# 5_Controller_A20_SSRs.net
KiCad netlist of a schematic drawn in Altium Designer
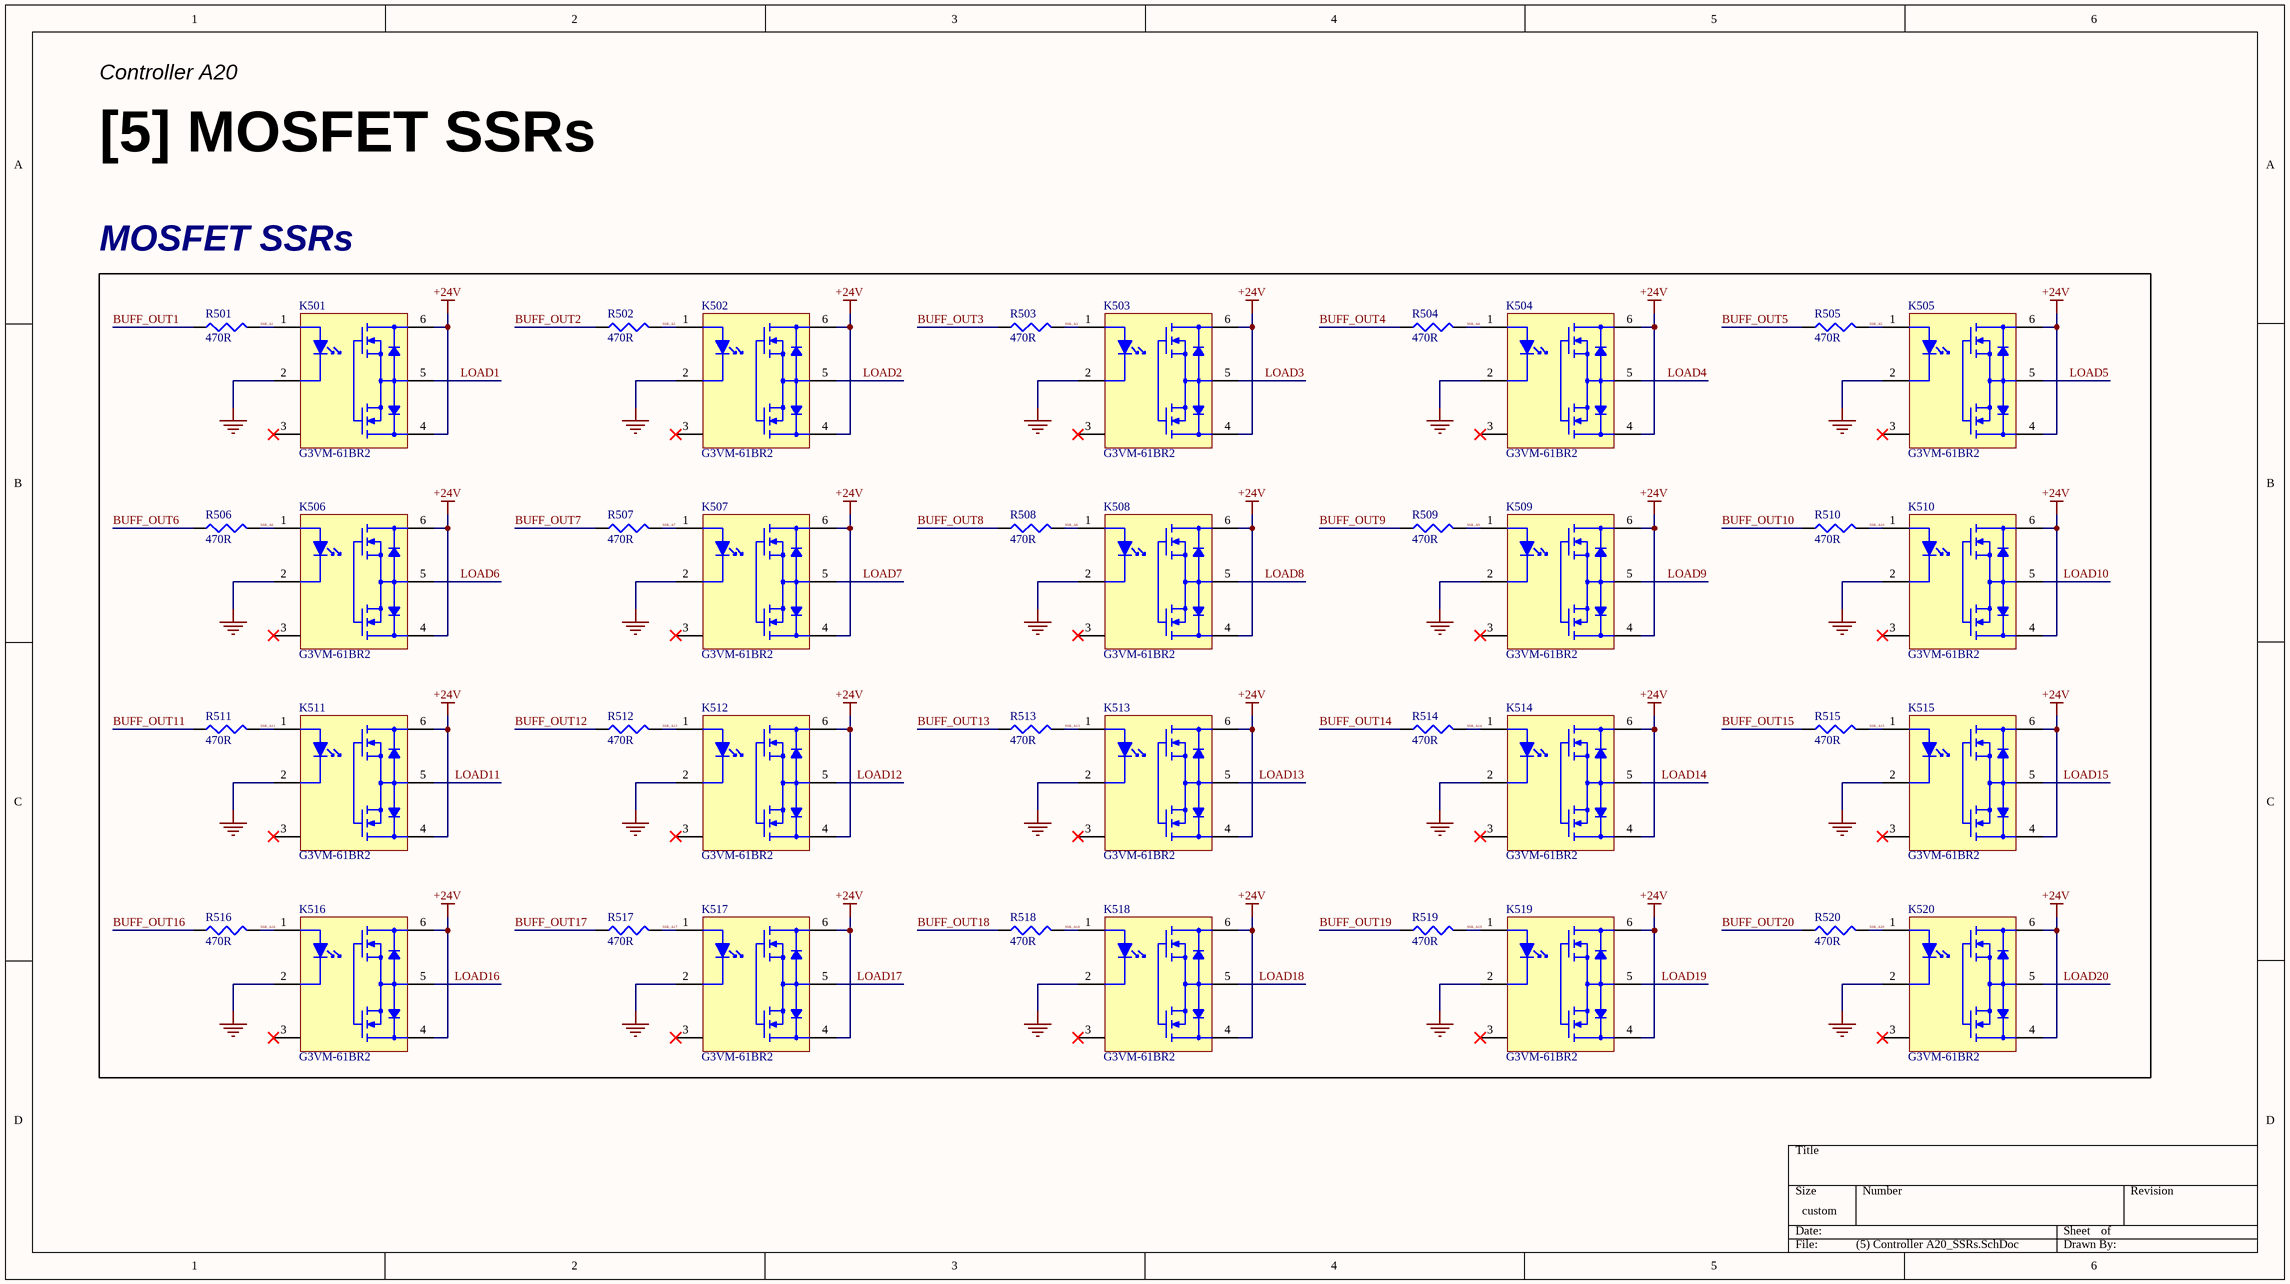
[diagram p0: (5) Controller A20_SSRs.SchDoc]

(export (version "E")
  (design (tool "Eeschema 10.0.6"))
  (components
    (comp (ref "K501")
      (value "G3VM-61BR2")
      (footprint "DIP6")
      (description "2.5kV 60V 1.64V DIP-6 Solid State Relays (SSR) RoHS")
      (fields (field (name "MANUFACTURER") "Omron Electronics Inc-EMC Div"))
      (libsource (lib "Symbols") (part "G3VM-61BR2 60V 4/8 A SSR"))
    )
    (comp (ref "K502")
      (value "G3VM-61BR2")
      (footprint "DIP6")
      (description "2.5kV 60V 1.64V DIP-6 Solid State Relays (SSR) RoHS")
      (fields (field (name "MANUFACTURER") "Omron Electronics Inc-EMC Div"))
      (libsource (lib "Symbols") (part "G3VM-61BR2 60V 4/8 A SSR"))
    )
    (comp (ref "K503")
      (value "G3VM-61BR2")
      (footprint "DIP6")
      (description "2.5kV 60V 1.64V DIP-6 Solid State Relays (SSR) RoHS")
      (fields (field (name "MANUFACTURER") "Omron Electronics Inc-EMC Div"))
      (libsource (lib "Symbols") (part "G3VM-61BR2 60V 4/8 A SSR"))
    )
    (comp (ref "K504")
      (value "G3VM-61BR2")
      (footprint "DIP6")
      (description "2.5kV 60V 1.64V DIP-6 Solid State Relays (SSR) RoHS")
      (fields (field (name "MANUFACTURER") "Omron Electronics Inc-EMC Div"))
      (libsource (lib "Symbols") (part "G3VM-61BR2 60V 4/8 A SSR"))
    )
    (comp (ref "K505")
      (value "G3VM-61BR2")
      (footprint "DIP6")
      (description "2.5kV 60V 1.64V DIP-6 Solid State Relays (SSR) RoHS")
      (fields (field (name "MANUFACTURER") "Omron Electronics Inc-EMC Div"))
      (libsource (lib "Symbols") (part "G3VM-61BR2 60V 4/8 A SSR"))
    )
    (comp (ref "K506")
      (value "G3VM-61BR2")
      (footprint "DIP6")
      (description "2.5kV 60V 1.64V DIP-6 Solid State Relays (SSR) RoHS")
      (fields (field (name "MANUFACTURER") "Omron Electronics Inc-EMC Div"))
      (libsource (lib "Symbols") (part "G3VM-61BR2 60V 4/8 A SSR"))
    )
    (comp (ref "K507")
      (value "G3VM-61BR2")
      (footprint "DIP6")
      (description "2.5kV 60V 1.64V DIP-6 Solid State Relays (SSR) RoHS")
      (fields (field (name "MANUFACTURER") "Omron Electronics Inc-EMC Div"))
      (libsource (lib "Symbols") (part "G3VM-61BR2 60V 4/8 A SSR"))
    )
    (comp (ref "K508")
      (value "G3VM-61BR2")
      (footprint "DIP6")
      (description "2.5kV 60V 1.64V DIP-6 Solid State Relays (SSR) RoHS")
      (fields (field (name "MANUFACTURER") "Omron Electronics Inc-EMC Div"))
      (libsource (lib "Symbols") (part "G3VM-61BR2 60V 4/8 A SSR"))
    )
    (comp (ref "K509")
      (value "G3VM-61BR2")
      (footprint "DIP6")
      (description "2.5kV 60V 1.64V DIP-6 Solid State Relays (SSR) RoHS")
      (fields (field (name "MANUFACTURER") "Omron Electronics Inc-EMC Div"))
      (libsource (lib "Symbols") (part "G3VM-61BR2 60V 4/8 A SSR"))
    )
    (comp (ref "K510")
      (value "G3VM-61BR2")
      (footprint "DIP6")
      (description "2.5kV 60V 1.64V DIP-6 Solid State Relays (SSR) RoHS")
      (fields (field (name "MANUFACTURER") "Omron Electronics Inc-EMC Div"))
      (libsource (lib "Symbols") (part "G3VM-61BR2 60V 4/8 A SSR"))
    )
    (comp (ref "K511")
      (value "G3VM-61BR2")
      (footprint "DIP6")
      (description "2.5kV 60V 1.64V DIP-6 Solid State Relays (SSR) RoHS")
      (fields (field (name "MANUFACTURER") "Omron Electronics Inc-EMC Div"))
      (libsource (lib "Symbols") (part "G3VM-61BR2 60V 4/8 A SSR"))
    )
    (comp (ref "K512")
      (value "G3VM-61BR2")
      (footprint "DIP6")
      (description "2.5kV 60V 1.64V DIP-6 Solid State Relays (SSR) RoHS")
      (fields (field (name "MANUFACTURER") "Omron Electronics Inc-EMC Div"))
      (libsource (lib "Symbols") (part "G3VM-61BR2 60V 4/8 A SSR"))
    )
    (comp (ref "K513")
      (value "G3VM-61BR2")
      (footprint "DIP6")
      (description "2.5kV 60V 1.64V DIP-6 Solid State Relays (SSR) RoHS")
      (fields (field (name "MANUFACTURER") "Omron Electronics Inc-EMC Div"))
      (libsource (lib "Symbols") (part "G3VM-61BR2 60V 4/8 A SSR"))
    )
    (comp (ref "K514")
      (value "G3VM-61BR2")
      (footprint "DIP6")
      (description "2.5kV 60V 1.64V DIP-6 Solid State Relays (SSR) RoHS")
      (fields (field (name "MANUFACTURER") "Omron Electronics Inc-EMC Div"))
      (libsource (lib "Symbols") (part "G3VM-61BR2 60V 4/8 A SSR"))
    )
    (comp (ref "K515")
      (value "G3VM-61BR2")
      (footprint "DIP6")
      (description "2.5kV 60V 1.64V DIP-6 Solid State Relays (SSR) RoHS")
      (fields (field (name "MANUFACTURER") "Omron Electronics Inc-EMC Div"))
      (libsource (lib "Symbols") (part "G3VM-61BR2 60V 4/8 A SSR"))
    )
    (comp (ref "K516")
      (value "G3VM-61BR2")
      (footprint "DIP6")
      (description "2.5kV 60V 1.64V DIP-6 Solid State Relays (SSR) RoHS")
      (fields (field (name "MANUFACTURER") "Omron Electronics Inc-EMC Div"))
      (libsource (lib "Symbols") (part "G3VM-61BR2 60V 4/8 A SSR"))
    )
    (comp (ref "K517")
      (value "G3VM-61BR2")
      (footprint "DIP6")
      (description "2.5kV 60V 1.64V DIP-6 Solid State Relays (SSR) RoHS")
      (fields (field (name "MANUFACTURER") "Omron Electronics Inc-EMC Div"))
      (libsource (lib "Symbols") (part "G3VM-61BR2 60V 4/8 A SSR"))
    )
    (comp (ref "K518")
      (value "G3VM-61BR2")
      (footprint "DIP6")
      (description "2.5kV 60V 1.64V DIP-6 Solid State Relays (SSR) RoHS")
      (fields (field (name "MANUFACTURER") "Omron Electronics Inc-EMC Div"))
      (libsource (lib "Symbols") (part "G3VM-61BR2 60V 4/8 A SSR"))
    )
    (comp (ref "K519")
      (value "G3VM-61BR2")
      (footprint "DIP6")
      (description "2.5kV 60V 1.64V DIP-6 Solid State Relays (SSR) RoHS")
      (fields (field (name "MANUFACTURER") "Omron Electronics Inc-EMC Div"))
      (libsource (lib "Symbols") (part "G3VM-61BR2 60V 4/8 A SSR"))
    )
    (comp (ref "K520")
      (value "G3VM-61BR2")
      (footprint "DIP6")
      (description "2.5kV 60V 1.64V DIP-6 Solid State Relays (SSR) RoHS")
      (fields (field (name "MANUFACTURER") "Omron Electronics Inc-EMC Div"))
      (libsource (lib "Symbols") (part "G3VM-61BR2 60V 4/8 A SSR"))
    )
    (comp (ref "R501")
      (value "470R")
      (footprint "R0603")
      (description "470 Ohms ±1% 0.1W, 1/10W Chip Resistor 0603 (1608 Metric) Thin Film")
      (fields (field (name "MANUFACTURER") "YAGEO") (field (name "MFR. PART #") "RT0603FRE07470RL"))
      (libsource (lib "Symbols") (part "RES 470R"))
    )
    (comp (ref "R502")
      (value "470R")
      (footprint "R0603")
      (description "470 Ohms ±1% 0.1W, 1/10W Chip Resistor 0603 (1608 Metric) Thin Film")
      (fields (field (name "MANUFACTURER") "YAGEO") (field (name "MFR. PART #") "RT0603FRE07470RL"))
      (libsource (lib "Symbols") (part "RES 470R"))
    )
    (comp (ref "R503")
      (value "470R")
      (footprint "R0603")
      (description "470 Ohms ±1% 0.1W, 1/10W Chip Resistor 0603 (1608 Metric) Thin Film")
      (fields (field (name "MANUFACTURER") "YAGEO") (field (name "MFR. PART #") "RT0603FRE07470RL"))
      (libsource (lib "Symbols") (part "RES 470R"))
    )
    (comp (ref "R504")
      (value "470R")
      (footprint "R0603")
      (description "470 Ohms ±1% 0.1W, 1/10W Chip Resistor 0603 (1608 Metric) Thin Film")
      (fields (field (name "MANUFACTURER") "YAGEO") (field (name "MFR. PART #") "RT0603FRE07470RL"))
      (libsource (lib "Symbols") (part "RES 470R"))
    )
    (comp (ref "R505")
      (value "470R")
      (footprint "R0603")
      (description "470 Ohms ±1% 0.1W, 1/10W Chip Resistor 0603 (1608 Metric) Thin Film")
      (fields (field (name "MANUFACTURER") "YAGEO") (field (name "MFR. PART #") "RT0603FRE07470RL"))
      (libsource (lib "Symbols") (part "RES 470R"))
    )
    (comp (ref "R506")
      (value "470R")
      (footprint "R0603")
      (description "470 Ohms ±1% 0.1W, 1/10W Chip Resistor 0603 (1608 Metric) Thin Film")
      (fields (field (name "MANUFACTURER") "YAGEO") (field (name "MFR. PART #") "RT0603FRE07470RL"))
      (libsource (lib "Symbols") (part "RES 470R"))
    )
    (comp (ref "R507")
      (value "470R")
      (footprint "R0603")
      (description "470 Ohms ±1% 0.1W, 1/10W Chip Resistor 0603 (1608 Metric) Thin Film")
      (fields (field (name "MANUFACTURER") "YAGEO") (field (name "MFR. PART #") "RT0603FRE07470RL"))
      (libsource (lib "Symbols") (part "RES 470R"))
    )
    (comp (ref "R508")
      (value "470R")
      (footprint "R0603")
      (description "470 Ohms ±1% 0.1W, 1/10W Chip Resistor 0603 (1608 Metric) Thin Film")
      (fields (field (name "MANUFACTURER") "YAGEO") (field (name "MFR. PART #") "RT0603FRE07470RL"))
      (libsource (lib "Symbols") (part "RES 470R"))
    )
    (comp (ref "R509")
      (value "470R")
      (footprint "R0603")
      (description "470 Ohms ±1% 0.1W, 1/10W Chip Resistor 0603 (1608 Metric) Thin Film")
      (fields (field (name "MANUFACTURER") "YAGEO") (field (name "MFR. PART #") "RT0603FRE07470RL"))
      (libsource (lib "Symbols") (part "RES 470R"))
    )
    (comp (ref "R510")
      (value "470R")
      (footprint "R0603")
      (description "470 Ohms ±1% 0.1W, 1/10W Chip Resistor 0603 (1608 Metric) Thin Film")
      (fields (field (name "MANUFACTURER") "YAGEO") (field (name "MFR. PART #") "RT0603FRE07470RL"))
      (libsource (lib "Symbols") (part "RES 470R"))
    )
    (comp (ref "R511")
      (value "470R")
      (footprint "R0603")
      (description "470 Ohms ±1% 0.1W, 1/10W Chip Resistor 0603 (1608 Metric) Thin Film")
      (fields (field (name "MANUFACTURER") "YAGEO") (field (name "MFR. PART #") "RT0603FRE07470RL"))
      (libsource (lib "Symbols") (part "RES 470R"))
    )
    (comp (ref "R512")
      (value "470R")
      (footprint "R0603")
      (description "470 Ohms ±1% 0.1W, 1/10W Chip Resistor 0603 (1608 Metric) Thin Film")
      (fields (field (name "MANUFACTURER") "YAGEO") (field (name "MFR. PART #") "RT0603FRE07470RL"))
      (libsource (lib "Symbols") (part "RES 470R"))
    )
    (comp (ref "R513")
      (value "470R")
      (footprint "R0603")
      (description "470 Ohms ±1% 0.1W, 1/10W Chip Resistor 0603 (1608 Metric) Thin Film")
      (fields (field (name "MANUFACTURER") "YAGEO") (field (name "MFR. PART #") "RT0603FRE07470RL"))
      (libsource (lib "Symbols") (part "RES 470R"))
    )
    (comp (ref "R514")
      (value "470R")
      (footprint "R0603")
      (description "470 Ohms ±1% 0.1W, 1/10W Chip Resistor 0603 (1608 Metric) Thin Film")
      (fields (field (name "MANUFACTURER") "YAGEO") (field (name "MFR. PART #") "RT0603FRE07470RL"))
      (libsource (lib "Symbols") (part "RES 470R"))
    )
    (comp (ref "R515")
      (value "470R")
      (footprint "R0603")
      (description "470 Ohms ±1% 0.1W, 1/10W Chip Resistor 0603 (1608 Metric) Thin Film")
      (fields (field (name "MANUFACTURER") "YAGEO") (field (name "MFR. PART #") "RT0603FRE07470RL"))
      (libsource (lib "Symbols") (part "RES 470R"))
    )
    (comp (ref "R516")
      (value "470R")
      (footprint "R0603")
      (description "470 Ohms ±1% 0.1W, 1/10W Chip Resistor 0603 (1608 Metric) Thin Film")
      (fields (field (name "MANUFACTURER") "YAGEO") (field (name "MFR. PART #") "RT0603FRE07470RL"))
      (libsource (lib "Symbols") (part "RES 470R"))
    )
    (comp (ref "R517")
      (value "470R")
      (footprint "R0603")
      (description "470 Ohms ±1% 0.1W, 1/10W Chip Resistor 0603 (1608 Metric) Thin Film")
      (fields (field (name "MANUFACTURER") "YAGEO") (field (name "MFR. PART #") "RT0603FRE07470RL"))
      (libsource (lib "Symbols") (part "RES 470R"))
    )
    (comp (ref "R518")
      (value "470R")
      (footprint "R0603")
      (description "470 Ohms ±1% 0.1W, 1/10W Chip Resistor 0603 (1608 Metric) Thin Film")
      (fields (field (name "MANUFACTURER") "YAGEO") (field (name "MFR. PART #") "RT0603FRE07470RL"))
      (libsource (lib "Symbols") (part "RES 470R"))
    )
    (comp (ref "R519")
      (value "470R")
      (footprint "R0603")
      (description "470 Ohms ±1% 0.1W, 1/10W Chip Resistor 0603 (1608 Metric) Thin Film")
      (fields (field (name "MANUFACTURER") "YAGEO") (field (name "MFR. PART #") "RT0603FRE07470RL"))
      (libsource (lib "Symbols") (part "RES 470R"))
    )
    (comp (ref "R520")
      (value "470R")
      (footprint "R0603")
      (description "470 Ohms ±1% 0.1W, 1/10W Chip Resistor 0603 (1608 Metric) Thin Film")
      (fields (field (name "MANUFACTURER") "YAGEO") (field (name "MFR. PART #") "RT0603FRE07470RL"))
      (libsource (lib "Symbols") (part "RES 470R"))
    )
  )
  (nets
    (net (code "1") (name "+24V") (class "Default")
      (node (ref "K501") (pin "4") (pinfunction "4_4") (pintype "power_in"))
      (node (ref "K501") (pin "6") (pinfunction "6_6") (pintype "power_in"))
      (node (ref "K502") (pin "4") (pinfunction "4_4") (pintype "power_in"))
      (node (ref "K502") (pin "6") (pinfunction "6_6") (pintype "power_in"))
      (node (ref "K503") (pin "4") (pinfunction "4_4") (pintype "power_in"))
      (node (ref "K503") (pin "6") (pinfunction "6_6") (pintype "power_in"))
      (node (ref "K504") (pin "4") (pinfunction "4_4") (pintype "power_in"))
      (node (ref "K504") (pin "6") (pinfunction "6_6") (pintype "power_in"))
      (node (ref "K505") (pin "4") (pinfunction "4_4") (pintype "power_in"))
      (node (ref "K505") (pin "6") (pinfunction "6_6") (pintype "power_in"))
      (node (ref "K506") (pin "4") (pinfunction "4_4") (pintype "power_in"))
      (node (ref "K506") (pin "6") (pinfunction "6_6") (pintype "power_in"))
      (node (ref "K507") (pin "4") (pinfunction "4_4") (pintype "power_in"))
      (node (ref "K507") (pin "6") (pinfunction "6_6") (pintype "power_in"))
      (node (ref "K508") (pin "4") (pinfunction "4_4") (pintype "power_in"))
      (node (ref "K508") (pin "6") (pinfunction "6_6") (pintype "power_in"))
      (node (ref "K509") (pin "4") (pinfunction "4_4") (pintype "power_in"))
      (node (ref "K509") (pin "6") (pinfunction "6_6") (pintype "power_in"))
      (node (ref "K510") (pin "4") (pinfunction "4_4") (pintype "power_in"))
      (node (ref "K510") (pin "6") (pinfunction "6_6") (pintype "power_in"))
      (node (ref "K511") (pin "4") (pinfunction "4_4") (pintype "power_in"))
      (node (ref "K511") (pin "6") (pinfunction "6_6") (pintype "power_in"))
      (node (ref "K512") (pin "4") (pinfunction "4_4") (pintype "power_in"))
      (node (ref "K512") (pin "6") (pinfunction "6_6") (pintype "power_in"))
      (node (ref "K513") (pin "4") (pinfunction "4_4") (pintype "power_in"))
      (node (ref "K513") (pin "6") (pinfunction "6_6") (pintype "power_in"))
      (node (ref "K514") (pin "4") (pinfunction "4_4") (pintype "power_in"))
      (node (ref "K514") (pin "6") (pinfunction "6_6") (pintype "power_in"))
      (node (ref "K515") (pin "4") (pinfunction "4_4") (pintype "power_in"))
      (node (ref "K515") (pin "6") (pinfunction "6_6") (pintype "power_in"))
      (node (ref "K516") (pin "4") (pinfunction "4_4") (pintype "power_in"))
      (node (ref "K516") (pin "6") (pinfunction "6_6") (pintype "power_in"))
      (node (ref "K517") (pin "4") (pinfunction "4_4") (pintype "power_in"))
      (node (ref "K517") (pin "6") (pinfunction "6_6") (pintype "power_in"))
      (node (ref "K518") (pin "4") (pinfunction "4_4") (pintype "power_in"))
      (node (ref "K518") (pin "6") (pinfunction "6_6") (pintype "power_in"))
      (node (ref "K519") (pin "4") (pinfunction "4_4") (pintype "power_in"))
      (node (ref "K519") (pin "6") (pinfunction "6_6") (pintype "power_in"))
      (node (ref "K520") (pin "4") (pinfunction "4_4") (pintype "power_in"))
      (node (ref "K520") (pin "6") (pinfunction "6_6") (pintype "power_in"))
    )
    (net (code "2") (name "/BUFF_OUT1") (class "Default")
      (node (ref "R501") (pin "1") (pinfunction "1_1") (pintype "passive"))
    )
    (net (code "3") (name "/BUFF_OUT2") (class "Default")
      (node (ref "R502") (pin "1") (pinfunction "1_1") (pintype "passive"))
    )
    (net (code "4") (name "/BUFF_OUT3") (class "Default")
      (node (ref "R503") (pin "1") (pinfunction "1_1") (pintype "passive"))
    )
    (net (code "5") (name "/BUFF_OUT4") (class "Default")
      (node (ref "R504") (pin "1") (pinfunction "1_1") (pintype "passive"))
    )
    (net (code "6") (name "/BUFF_OUT5") (class "Default")
      (node (ref "R505") (pin "1") (pinfunction "1_1") (pintype "passive"))
    )
    (net (code "7") (name "/BUFF_OUT6") (class "Default")
      (node (ref "R506") (pin "1") (pinfunction "1_1") (pintype "passive"))
    )
    (net (code "8") (name "/BUFF_OUT7") (class "Default")
      (node (ref "R507") (pin "1") (pinfunction "1_1") (pintype "passive"))
    )
    (net (code "9") (name "/BUFF_OUT8") (class "Default")
      (node (ref "R508") (pin "1") (pinfunction "1_1") (pintype "passive"))
    )
    (net (code "10") (name "/BUFF_OUT9") (class "Default")
      (node (ref "R509") (pin "1") (pinfunction "1_1") (pintype "passive"))
    )
    (net (code "11") (name "/BUFF_OUT10") (class "Default")
      (node (ref "R510") (pin "1") (pinfunction "1_1") (pintype "passive"))
    )
    (net (code "12") (name "/BUFF_OUT11") (class "Default")
      (node (ref "R511") (pin "1") (pinfunction "1_1") (pintype "passive"))
    )
    (net (code "13") (name "/BUFF_OUT12") (class "Default")
      (node (ref "R512") (pin "1") (pinfunction "1_1") (pintype "passive"))
    )
    (net (code "14") (name "/BUFF_OUT13") (class "Default")
      (node (ref "R513") (pin "1") (pinfunction "1_1") (pintype "passive"))
    )
    (net (code "15") (name "/BUFF_OUT14") (class "Default")
      (node (ref "R514") (pin "1") (pinfunction "1_1") (pintype "passive"))
    )
    (net (code "16") (name "/BUFF_OUT15") (class "Default")
      (node (ref "R515") (pin "1") (pinfunction "1_1") (pintype "passive"))
    )
    (net (code "17") (name "/BUFF_OUT16") (class "Default")
      (node (ref "R516") (pin "1") (pinfunction "1_1") (pintype "passive"))
    )
    (net (code "18") (name "/BUFF_OUT17") (class "Default")
      (node (ref "R517") (pin "1") (pinfunction "1_1") (pintype "passive"))
    )
    (net (code "19") (name "/BUFF_OUT18") (class "Default")
      (node (ref "R518") (pin "1") (pinfunction "1_1") (pintype "passive"))
    )
    (net (code "20") (name "/BUFF_OUT19") (class "Default")
      (node (ref "R519") (pin "1") (pinfunction "1_1") (pintype "passive"))
    )
    (net (code "21") (name "/BUFF_OUT20") (class "Default")
      (node (ref "R520") (pin "1") (pinfunction "1_1") (pintype "passive"))
    )
    (net (code "22") (name "/LOAD1") (class "Default")
      (node (ref "K501") (pin "5") (pinfunction "5_5") (pintype "power_in"))
    )
    (net (code "23") (name "/LOAD2") (class "Default")
      (node (ref "K502") (pin "5") (pinfunction "5_5") (pintype "power_in"))
    )
    (net (code "24") (name "/LOAD3") (class "Default")
      (node (ref "K503") (pin "5") (pinfunction "5_5") (pintype "power_in"))
    )
    (net (code "25") (name "/LOAD4") (class "Default")
      (node (ref "K504") (pin "5") (pinfunction "5_5") (pintype "power_in"))
    )
    (net (code "26") (name "/LOAD5") (class "Default")
      (node (ref "K505") (pin "5") (pinfunction "5_5") (pintype "power_in"))
    )
    (net (code "27") (name "/LOAD6") (class "Default")
      (node (ref "K506") (pin "5") (pinfunction "5_5") (pintype "power_in"))
    )
    (net (code "28") (name "/LOAD7") (class "Default")
      (node (ref "K507") (pin "5") (pinfunction "5_5") (pintype "power_in"))
    )
    (net (code "29") (name "/LOAD8") (class "Default")
      (node (ref "K508") (pin "5") (pinfunction "5_5") (pintype "power_in"))
    )
    (net (code "30") (name "/LOAD9") (class "Default")
      (node (ref "K509") (pin "5") (pinfunction "5_5") (pintype "power_in"))
    )
    (net (code "31") (name "/LOAD10") (class "Default")
      (node (ref "K510") (pin "5") (pinfunction "5_5") (pintype "power_in"))
    )
    (net (code "32") (name "/LOAD11") (class "Default")
      (node (ref "K511") (pin "5") (pinfunction "5_5") (pintype "power_in"))
    )
    (net (code "33") (name "/LOAD12") (class "Default")
      (node (ref "K512") (pin "5") (pinfunction "5_5") (pintype "power_in"))
    )
    (net (code "34") (name "/LOAD13") (class "Default")
      (node (ref "K513") (pin "5") (pinfunction "5_5") (pintype "power_in"))
    )
    (net (code "35") (name "/LOAD14") (class "Default")
      (node (ref "K514") (pin "5") (pinfunction "5_5") (pintype "power_in"))
    )
    (net (code "36") (name "/LOAD15") (class "Default")
      (node (ref "K515") (pin "5") (pinfunction "5_5") (pintype "power_in"))
    )
    (net (code "37") (name "/LOAD16") (class "Default")
      (node (ref "K516") (pin "5") (pinfunction "5_5") (pintype "power_in"))
    )
    (net (code "38") (name "/LOAD17") (class "Default")
      (node (ref "K517") (pin "5") (pinfunction "5_5") (pintype "power_in"))
    )
    (net (code "39") (name "/LOAD18") (class "Default")
      (node (ref "K518") (pin "5") (pinfunction "5_5") (pintype "power_in"))
    )
    (net (code "40") (name "/LOAD19") (class "Default")
      (node (ref "K519") (pin "5") (pinfunction "5_5") (pintype "power_in"))
    )
    (net (code "41") (name "/LOAD20") (class "Default")
      (node (ref "K520") (pin "5") (pinfunction "5_5") (pintype "power_in"))
    )
    (net (code "42") (name "/SSR_A1") (class "Default")
      (node (ref "K501") (pin "1") (pinfunction "1_1") (pintype "passive"))
      (node (ref "R501") (pin "2") (pinfunction "2_2") (pintype "passive"))
    )
    (net (code "43") (name "/SSR_A2") (class "Default")
      (node (ref "K502") (pin "1") (pinfunction "1_1") (pintype "passive"))
      (node (ref "R502") (pin "2") (pinfunction "2_2") (pintype "passive"))
    )
    (net (code "44") (name "/SSR_A3") (class "Default")
      (node (ref "K503") (pin "1") (pinfunction "1_1") (pintype "passive"))
      (node (ref "R503") (pin "2") (pinfunction "2_2") (pintype "passive"))
    )
    (net (code "45") (name "/SSR_A4") (class "Default")
      (node (ref "K504") (pin "1") (pinfunction "1_1") (pintype "passive"))
      (node (ref "R504") (pin "2") (pinfunction "2_2") (pintype "passive"))
    )
    (net (code "46") (name "/SSR_A5") (class "Default")
      (node (ref "K505") (pin "1") (pinfunction "1_1") (pintype "passive"))
      (node (ref "R505") (pin "2") (pinfunction "2_2") (pintype "passive"))
    )
    (net (code "47") (name "/SSR_A6") (class "Default")
      (node (ref "K506") (pin "1") (pinfunction "1_1") (pintype "passive"))
      (node (ref "R506") (pin "2") (pinfunction "2_2") (pintype "passive"))
    )
    (net (code "48") (name "/SSR_A7") (class "Default")
      (node (ref "K507") (pin "1") (pinfunction "1_1") (pintype "passive"))
      (node (ref "R507") (pin "2") (pinfunction "2_2") (pintype "passive"))
    )
    (net (code "49") (name "/SSR_A8") (class "Default")
      (node (ref "K508") (pin "1") (pinfunction "1_1") (pintype "passive"))
      (node (ref "R508") (pin "2") (pinfunction "2_2") (pintype "passive"))
    )
    (net (code "50") (name "/SSR_A9") (class "Default")
      (node (ref "K509") (pin "1") (pinfunction "1_1") (pintype "passive"))
      (node (ref "R509") (pin "2") (pinfunction "2_2") (pintype "passive"))
    )
    (net (code "51") (name "/SSR_A10") (class "Default")
      (node (ref "K510") (pin "1") (pinfunction "1_1") (pintype "passive"))
      (node (ref "R510") (pin "2") (pinfunction "2_2") (pintype "passive"))
    )
    (net (code "52") (name "/SSR_A11") (class "Default")
      (node (ref "K511") (pin "1") (pinfunction "1_1") (pintype "passive"))
      (node (ref "R511") (pin "2") (pinfunction "2_2") (pintype "passive"))
    )
    (net (code "53") (name "/SSR_A12") (class "Default")
      (node (ref "K512") (pin "1") (pinfunction "1_1") (pintype "passive"))
      (node (ref "R512") (pin "2") (pinfunction "2_2") (pintype "passive"))
    )
    (net (code "54") (name "/SSR_A13") (class "Default")
      (node (ref "K513") (pin "1") (pinfunction "1_1") (pintype "passive"))
      (node (ref "R513") (pin "2") (pinfunction "2_2") (pintype "passive"))
    )
    (net (code "55") (name "/SSR_A14") (class "Default")
      (node (ref "K514") (pin "1") (pinfunction "1_1") (pintype "passive"))
      (node (ref "R514") (pin "2") (pinfunction "2_2") (pintype "passive"))
    )
    (net (code "56") (name "/SSR_A15") (class "Default")
      (node (ref "K515") (pin "1") (pinfunction "1_1") (pintype "passive"))
      (node (ref "R515") (pin "2") (pinfunction "2_2") (pintype "passive"))
    )
    (net (code "57") (name "/SSR_A16") (class "Default")
      (node (ref "K516") (pin "1") (pinfunction "1_1") (pintype "passive"))
      (node (ref "R516") (pin "2") (pinfunction "2_2") (pintype "passive"))
    )
    (net (code "58") (name "/SSR_A17") (class "Default")
      (node (ref "K517") (pin "1") (pinfunction "1_1") (pintype "passive"))
      (node (ref "R517") (pin "2") (pinfunction "2_2") (pintype "passive"))
    )
    (net (code "59") (name "/SSR_A18") (class "Default")
      (node (ref "K518") (pin "1") (pinfunction "1_1") (pintype "passive"))
      (node (ref "R518") (pin "2") (pinfunction "2_2") (pintype "passive"))
    )
    (net (code "60") (name "/SSR_A19") (class "Default")
      (node (ref "K519") (pin "1") (pinfunction "1_1") (pintype "passive"))
      (node (ref "R519") (pin "2") (pinfunction "2_2") (pintype "passive"))
    )
    (net (code "61") (name "/SSR_A20") (class "Default")
      (node (ref "K520") (pin "1") (pinfunction "1_1") (pintype "passive"))
      (node (ref "R520") (pin "2") (pinfunction "2_2") (pintype "passive"))
    )
    (net (code "62") (name "GND") (class "Default")
      (node (ref "K501") (pin "2") (pinfunction "2_2") (pintype "passive"))
      (node (ref "K502") (pin "2") (pinfunction "2_2") (pintype "passive"))
      (node (ref "K503") (pin "2") (pinfunction "2_2") (pintype "passive"))
      (node (ref "K504") (pin "2") (pinfunction "2_2") (pintype "passive"))
      (node (ref "K505") (pin "2") (pinfunction "2_2") (pintype "passive"))
      (node (ref "K506") (pin "2") (pinfunction "2_2") (pintype "passive"))
      (node (ref "K507") (pin "2") (pinfunction "2_2") (pintype "passive"))
      (node (ref "K508") (pin "2") (pinfunction "2_2") (pintype "passive"))
      (node (ref "K509") (pin "2") (pinfunction "2_2") (pintype "passive"))
      (node (ref "K510") (pin "2") (pinfunction "2_2") (pintype "passive"))
      (node (ref "K511") (pin "2") (pinfunction "2_2") (pintype "passive"))
      (node (ref "K512") (pin "2") (pinfunction "2_2") (pintype "passive"))
      (node (ref "K513") (pin "2") (pinfunction "2_2") (pintype "passive"))
      (node (ref "K514") (pin "2") (pinfunction "2_2") (pintype "passive"))
      (node (ref "K515") (pin "2") (pinfunction "2_2") (pintype "passive"))
      (node (ref "K516") (pin "2") (pinfunction "2_2") (pintype "passive"))
      (node (ref "K517") (pin "2") (pinfunction "2_2") (pintype "passive"))
      (node (ref "K518") (pin "2") (pinfunction "2_2") (pintype "passive"))
      (node (ref "K519") (pin "2") (pinfunction "2_2") (pintype "passive"))
      (node (ref "K520") (pin "2") (pinfunction "2_2") (pintype "passive"))
    )
    (net (code "63") (name "unconnected-(K501-Pad3)") (class "Default")
      (node (ref "K501") (pin "3") (pinfunction "3_3") (pintype "tri_state+no_connect"))
    )
    (net (code "64") (name "unconnected-(K502-Pad3)") (class "Default")
      (node (ref "K502") (pin "3") (pinfunction "3_3") (pintype "tri_state+no_connect"))
    )
    (net (code "65") (name "unconnected-(K503-Pad3)") (class "Default")
      (node (ref "K503") (pin "3") (pinfunction "3_3") (pintype "tri_state+no_connect"))
    )
    (net (code "66") (name "unconnected-(K504-Pad3)") (class "Default")
      (node (ref "K504") (pin "3") (pinfunction "3_3") (pintype "tri_state+no_connect"))
    )
    (net (code "67") (name "unconnected-(K505-Pad3)") (class "Default")
      (node (ref "K505") (pin "3") (pinfunction "3_3") (pintype "tri_state+no_connect"))
    )
    (net (code "68") (name "unconnected-(K506-Pad3)") (class "Default")
      (node (ref "K506") (pin "3") (pinfunction "3_3") (pintype "tri_state+no_connect"))
    )
    (net (code "69") (name "unconnected-(K507-Pad3)") (class "Default")
      (node (ref "K507") (pin "3") (pinfunction "3_3") (pintype "tri_state+no_connect"))
    )
    (net (code "70") (name "unconnected-(K508-Pad3)") (class "Default")
      (node (ref "K508") (pin "3") (pinfunction "3_3") (pintype "tri_state+no_connect"))
    )
    (net (code "71") (name "unconnected-(K509-Pad3)") (class "Default")
      (node (ref "K509") (pin "3") (pinfunction "3_3") (pintype "tri_state+no_connect"))
    )
    (net (code "72") (name "unconnected-(K510-Pad3)") (class "Default")
      (node (ref "K510") (pin "3") (pinfunction "3_3") (pintype "tri_state+no_connect"))
    )
    (net (code "73") (name "unconnected-(K511-Pad3)") (class "Default")
      (node (ref "K511") (pin "3") (pinfunction "3_3") (pintype "tri_state+no_connect"))
    )
    (net (code "74") (name "unconnected-(K512-Pad3)") (class "Default")
      (node (ref "K512") (pin "3") (pinfunction "3_3") (pintype "tri_state+no_connect"))
    )
    (net (code "75") (name "unconnected-(K513-Pad3)") (class "Default")
      (node (ref "K513") (pin "3") (pinfunction "3_3") (pintype "tri_state+no_connect"))
    )
    (net (code "76") (name "unconnected-(K514-Pad3)") (class "Default")
      (node (ref "K514") (pin "3") (pinfunction "3_3") (pintype "tri_state+no_connect"))
    )
    (net (code "77") (name "unconnected-(K515-Pad3)") (class "Default")
      (node (ref "K515") (pin "3") (pinfunction "3_3") (pintype "tri_state+no_connect"))
    )
    (net (code "78") (name "unconnected-(K516-Pad3)") (class "Default")
      (node (ref "K516") (pin "3") (pinfunction "3_3") (pintype "tri_state+no_connect"))
    )
    (net (code "79") (name "unconnected-(K517-Pad3)") (class "Default")
      (node (ref "K517") (pin "3") (pinfunction "3_3") (pintype "tri_state+no_connect"))
    )
    (net (code "80") (name "unconnected-(K518-Pad3)") (class "Default")
      (node (ref "K518") (pin "3") (pinfunction "3_3") (pintype "tri_state+no_connect"))
    )
    (net (code "81") (name "unconnected-(K519-Pad3)") (class "Default")
      (node (ref "K519") (pin "3") (pinfunction "3_3") (pintype "tri_state+no_connect"))
    )
    (net (code "82") (name "unconnected-(K520-Pad3)") (class "Default")
      (node (ref "K520") (pin "3") (pinfunction "3_3") (pintype "tri_state+no_connect"))
    )
  )
)
